# Rex2016.net
KiCad netlist of a schematic drawn in EAGLE
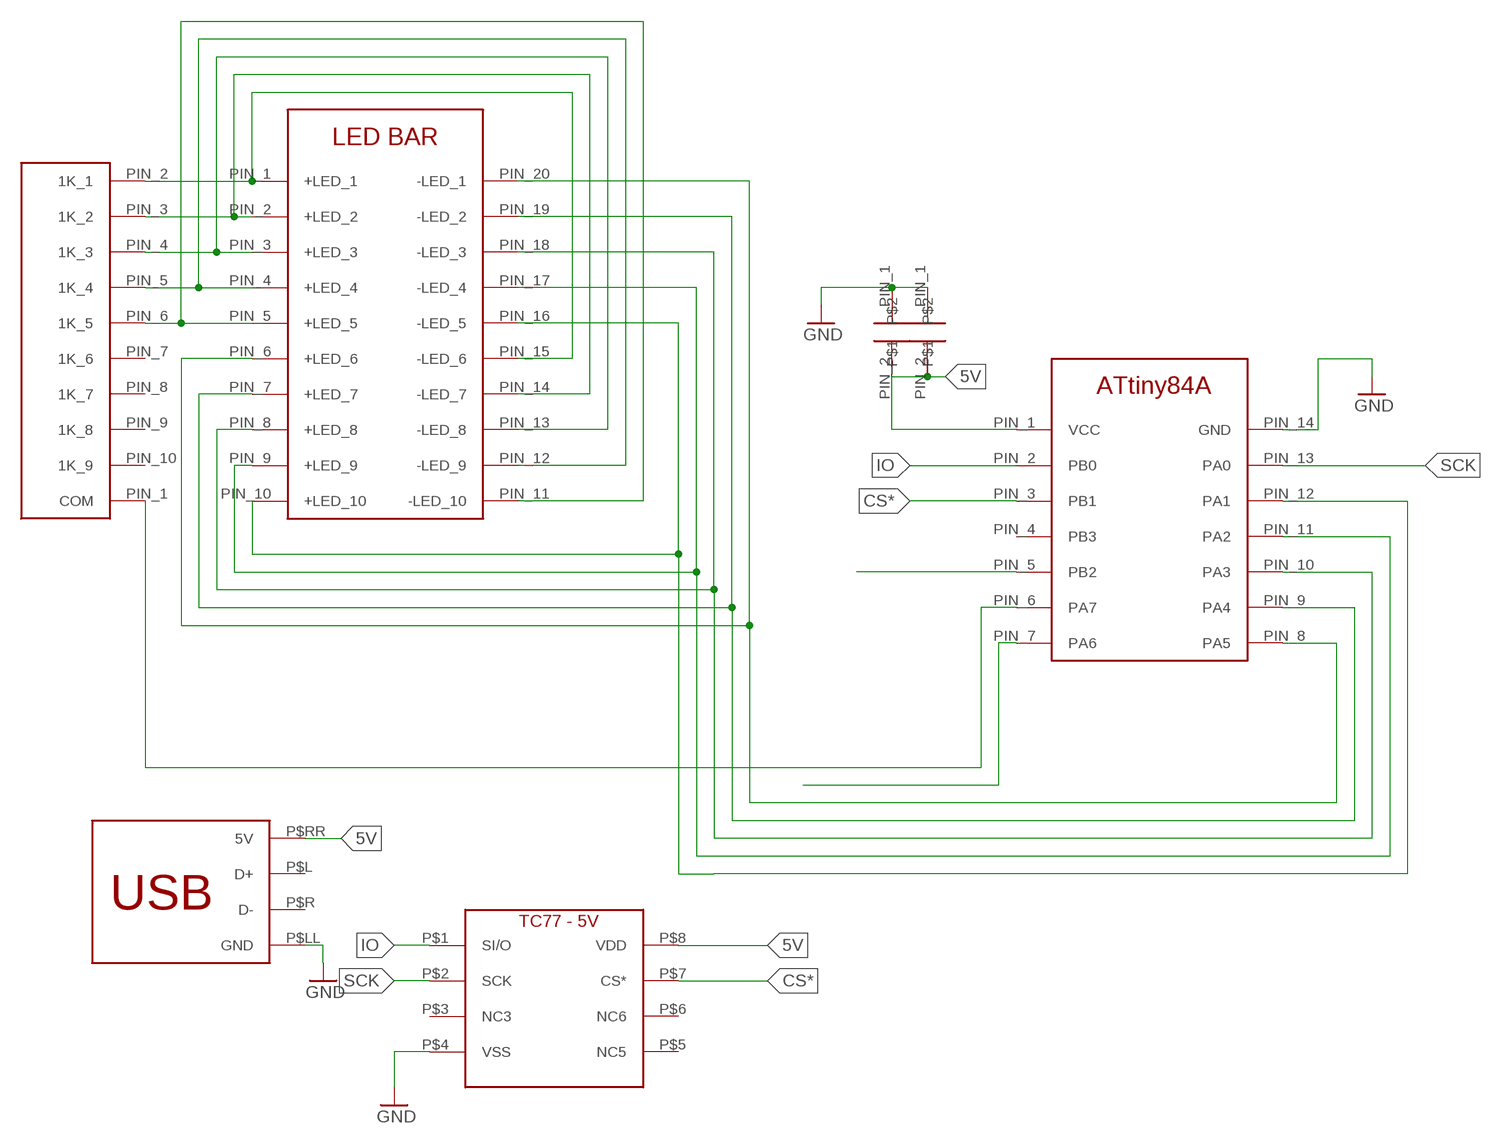
[diagram p0: schematic, sheet 1]

(export (version "E")
  (design (tool "Eeschema 10.0.6"))
  (components
    (comp (ref "U$1")
      (value "9X_1K_BUSSED_R")
      (footprint "eagle-import:SIP-10")
      (libsource (lib "eagle-import") (part "9X_1K_BUSSED_R"))
    )
    (comp (ref "U$2")
      (value "10UF_FK18")
      (footprint "eagle-import:CAP_FK18")
      (libsource (lib "eagle-import") (part "10UF_FK18"))
    )
    (comp (ref "U$3")
      (value "ATTINY84A")
      (footprint "eagle-import:PDIP-14")
      (libsource (lib "eagle-import") (part "ATTINY84A"))
    )
    (comp (ref "U$4")
      (value "LED_X10_BAR")
      (footprint "eagle-import:LED_X10_BAR")
      (libsource (lib "eagle-import") (part "LED_X10_BAR"))
    )
    (comp (ref "U$5")
      (value "TC77")
      (footprint "eagle-import:SOIC-8")
      (libsource (lib "eagle-import") (part "TC77"))
    )
    (comp (ref "U$6")
      (value "10UF_FK18")
      (footprint "eagle-import:CAP_FK18")
      (libsource (lib "eagle-import") (part "10UF_FK18"))
    )
    (comp (ref "U$7")
      (value "USB_A_TH")
      (footprint "eagle-import:USB_A_TH")
      (libsource (lib "eagle-import") (part "USB_A_TH"))
    )
  )
  (nets
    (net (code "1") (name "5V") (class "Default")
      (node (ref "U$2") (pin "PIN_2") (pinfunction "P$2_PIN_2") (pintype "bidirectional"))
      (node (ref "U$3") (pin "PIN_1") (pinfunction "VCC_PIN_1") (pintype "bidirectional"))
      (node (ref "U$5") (pin "P$8") (pinfunction "VDD_P$8") (pintype "bidirectional"))
      (node (ref "U$6") (pin "PIN_2") (pinfunction "P$2_PIN_2") (pintype "bidirectional"))
      (node (ref "U$7") (pin "P$RR") (pinfunction "5V_P$RR") (pintype "bidirectional"))
    )
    (net (code "2") (name "CS*") (class "Default")
      (node (ref "U$3") (pin "PIN_3") (pinfunction "PB1_PIN_3") (pintype "bidirectional"))
      (node (ref "U$5") (pin "P$7") (pinfunction "CS*_P$7") (pintype "bidirectional"))
    )
    (net (code "3") (name "GND") (class "Default")
      (node (ref "U$2") (pin "PIN_1") (pinfunction "P$1_PIN_1") (pintype "bidirectional"))
      (node (ref "U$3") (pin "PIN_14") (pinfunction "GND_PIN_14") (pintype "bidirectional"))
      (node (ref "U$5") (pin "P$4") (pinfunction "VSS_P$4") (pintype "bidirectional"))
      (node (ref "U$6") (pin "PIN_1") (pinfunction "P$1_PIN_1") (pintype "bidirectional"))
      (node (ref "U$7") (pin "P$LL") (pinfunction "GND_P$LL") (pintype "bidirectional"))
    )
    (net (code "4") (name "IO") (class "Default")
      (node (ref "U$3") (pin "PIN_2") (pinfunction "PB0_PIN_2") (pintype "bidirectional"))
      (node (ref "U$5") (pin "P$1") (pinfunction "SI/O_P$1") (pintype "bidirectional"))
    )
    (net (code "5") (name "Net-(U$1-1K_1)") (class "Default")
      (node (ref "U$1") (pin "PIN_2") (pinfunction "1K_1_PIN_2") (pintype "bidirectional"))
      (node (ref "U$4") (pin "PIN_1") (pinfunction "+LED_1_PIN_1") (pintype "bidirectional"))
      (node (ref "U$4") (pin "PIN_15") (pinfunction "-LED_6_PIN_15") (pintype "bidirectional"))
    )
    (net (code "6") (name "Net-(U$1-1K_2)") (class "Default")
      (node (ref "U$1") (pin "PIN_3") (pinfunction "1K_2_PIN_3") (pintype "bidirectional"))
      (node (ref "U$4") (pin "PIN_14") (pinfunction "-LED_7_PIN_14") (pintype "bidirectional"))
      (node (ref "U$4") (pin "PIN_2") (pinfunction "+LED_2_PIN_2") (pintype "bidirectional"))
    )
    (net (code "7") (name "Net-(U$1-1K_3)") (class "Default")
      (node (ref "U$1") (pin "PIN_4") (pinfunction "1K_3_PIN_4") (pintype "bidirectional"))
      (node (ref "U$4") (pin "PIN_13") (pinfunction "-LED_8_PIN_13") (pintype "bidirectional"))
      (node (ref "U$4") (pin "PIN_3") (pinfunction "+LED_3_PIN_3") (pintype "bidirectional"))
    )
    (net (code "8") (name "Net-(U$1-1K_4)") (class "Default")
      (node (ref "U$1") (pin "PIN_5") (pinfunction "1K_4_PIN_5") (pintype "bidirectional"))
      (node (ref "U$4") (pin "PIN_12") (pinfunction "-LED_9_PIN_12") (pintype "bidirectional"))
      (node (ref "U$4") (pin "PIN_4") (pinfunction "+LED_4_PIN_4") (pintype "bidirectional"))
    )
    (net (code "9") (name "Net-(U$1-1K_5)") (class "Default")
      (node (ref "U$1") (pin "PIN_6") (pinfunction "1K_5_PIN_6") (pintype "bidirectional"))
      (node (ref "U$4") (pin "PIN_11") (pinfunction "-LED_10_PIN_11") (pintype "bidirectional"))
      (node (ref "U$4") (pin "PIN_5") (pinfunction "+LED_5_PIN_5") (pintype "bidirectional"))
    )
    (net (code "10") (name "Net-(U$1-COM)") (class "Default")
      (node (ref "U$1") (pin "PIN_1") (pinfunction "COM_PIN_1") (pintype "bidirectional"))
      (node (ref "U$3") (pin "PIN_6") (pinfunction "PA7_PIN_6") (pintype "bidirectional"))
    )
    (net (code "11") (name "Net-(U$3-PA1)") (class "Default")
      (node (ref "U$3") (pin "PIN_12") (pinfunction "PA1_PIN_12") (pintype "bidirectional"))
      (node (ref "U$4") (pin "PIN_10") (pinfunction "+LED_10_PIN_10") (pintype "bidirectional"))
      (node (ref "U$4") (pin "PIN_16") (pinfunction "-LED_5_PIN_16") (pintype "bidirectional"))
    )
    (net (code "12") (name "Net-(U$3-PA2)") (class "Default")
      (node (ref "U$3") (pin "PIN_11") (pinfunction "PA2_PIN_11") (pintype "bidirectional"))
      (node (ref "U$4") (pin "PIN_17") (pinfunction "-LED_4_PIN_17") (pintype "bidirectional"))
      (node (ref "U$4") (pin "PIN_9") (pinfunction "+LED_9_PIN_9") (pintype "bidirectional"))
    )
    (net (code "13") (name "Net-(U$3-PA3)") (class "Default")
      (node (ref "U$3") (pin "PIN_10") (pinfunction "PA3_PIN_10") (pintype "bidirectional"))
      (node (ref "U$4") (pin "PIN_18") (pinfunction "-LED_3_PIN_18") (pintype "bidirectional"))
      (node (ref "U$4") (pin "PIN_8") (pinfunction "+LED_8_PIN_8") (pintype "bidirectional"))
    )
    (net (code "14") (name "Net-(U$3-PA4)") (class "Default")
      (node (ref "U$3") (pin "PIN_9") (pinfunction "PA4_PIN_9") (pintype "bidirectional"))
      (node (ref "U$4") (pin "PIN_19") (pinfunction "-LED_2_PIN_19") (pintype "bidirectional"))
      (node (ref "U$4") (pin "PIN_7") (pinfunction "+LED_7_PIN_7") (pintype "bidirectional"))
    )
    (net (code "15") (name "Net-(U$3-PA5)") (class "Default")
      (node (ref "U$3") (pin "PIN_8") (pinfunction "PA5_PIN_8") (pintype "bidirectional"))
      (node (ref "U$4") (pin "PIN_20") (pinfunction "-LED_1_PIN_20") (pintype "bidirectional"))
      (node (ref "U$4") (pin "PIN_6") (pinfunction "+LED_6_PIN_6") (pintype "bidirectional"))
    )
    (net (code "16") (name "SCK") (class "Default")
      (node (ref "U$3") (pin "PIN_13") (pinfunction "PA0_PIN_13") (pintype "bidirectional"))
      (node (ref "U$5") (pin "P$2") (pinfunction "SCK_P$2") (pintype "bidirectional"))
    )
    (net (code "17") (name "unconnected-(U$1-1K_6-PadPIN_7)") (class "Default")
      (node (ref "U$1") (pin "PIN_7") (pinfunction "1K_6_PIN_7") (pintype "bidirectional"))
    )
    (net (code "18") (name "unconnected-(U$1-1K_7-PadPIN_8)") (class "Default")
      (node (ref "U$1") (pin "PIN_8") (pinfunction "1K_7_PIN_8") (pintype "bidirectional"))
    )
    (net (code "19") (name "unconnected-(U$1-1K_8-PadPIN_9)") (class "Default")
      (node (ref "U$1") (pin "PIN_9") (pinfunction "1K_8_PIN_9") (pintype "bidirectional"))
    )
    (net (code "20") (name "unconnected-(U$1-1K_9-PadPIN_10)") (class "Default")
      (node (ref "U$1") (pin "PIN_10") (pinfunction "1K_9_PIN_10") (pintype "bidirectional"))
    )
    (net (code "21") (name "unconnected-(U$3-PA6-PadPIN_7)") (class "Default")
      (node (ref "U$3") (pin "PIN_7") (pinfunction "PA6_PIN_7") (pintype "bidirectional"))
    )
    (net (code "22") (name "unconnected-(U$3-PB2-PadPIN_5)") (class "Default")
      (node (ref "U$3") (pin "PIN_5") (pinfunction "PB2_PIN_5") (pintype "bidirectional"))
    )
    (net (code "23") (name "unconnected-(U$3-PB3-PadPIN_4)") (class "Default")
      (node (ref "U$3") (pin "PIN_4") (pinfunction "PB3_PIN_4") (pintype "bidirectional"))
    )
    (net (code "24") (name "unconnected-(U$5-NC3-PadP$3)") (class "Default")
      (node (ref "U$5") (pin "P$3") (pinfunction "NC3_P$3") (pintype "bidirectional"))
    )
    (net (code "25") (name "unconnected-(U$5-NC5-PadP$5)") (class "Default")
      (node (ref "U$5") (pin "P$5") (pinfunction "NC5_P$5") (pintype "bidirectional"))
    )
    (net (code "26") (name "unconnected-(U$5-NC6-PadP$6)") (class "Default")
      (node (ref "U$5") (pin "P$6") (pinfunction "NC6_P$6") (pintype "bidirectional"))
    )
    (net (code "27") (name "unconnected-(U$7-D+-PadP$L)") (class "Default")
      (node (ref "U$7") (pin "P$L") (pinfunction "D+_P$L") (pintype "bidirectional"))
    )
    (net (code "28") (name "unconnected-(U$7-D--PadP$R)") (class "Default")
      (node (ref "U$7") (pin "P$R") (pinfunction "D-_P$R") (pintype "bidirectional"))
    )
  )
)
